# Drones_Schematic_Headers.net
KiCad netlist of a schematic drawn in EAGLE
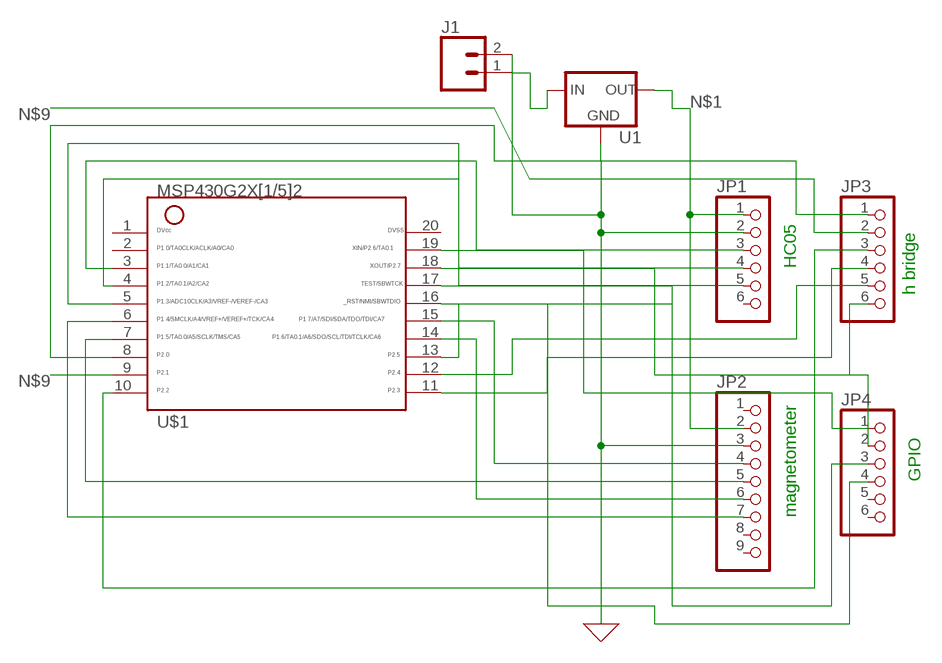
[diagram p0: schematic, sheet 1]

(export (version "E")
  (design (tool "Eeschema 10.0.6"))
  (components
    (comp (ref "J1")
      (value "CONN_025MM")
      (footprint "eagle-import:SCREWTERMINAL-5MM-2")
      (libsource (lib "eagle-import") (part "CONN_025MM"))
    )
    (comp (ref "JP1")
      (value "PINHD-1X6")
      (footprint "eagle-import:1X06")
      (libsource (lib "eagle-import") (part "PINHD-1X6"))
    )
    (comp (ref "JP2")
      (value "PINHD-1X9")
      (footprint "eagle-import:1X09-BIG")
      (libsource (lib "eagle-import") (part "PINHD-1X9"))
    )
    (comp (ref "JP3")
      (value "PINHD-1X6")
      (footprint "eagle-import:1X06")
      (libsource (lib "eagle-import") (part "PINHD-1X6"))
    )
    (comp (ref "JP4")
      (value "PINHD-1X6")
      (footprint "eagle-import:1X06")
      (libsource (lib "eagle-import") (part "PINHD-1X6"))
    )
    (comp (ref "U$1")
      (value "G2X[1/5]2---N20")
      (footprint "eagle-import:N20")
      (libsource (lib "eagle-import") (part "G2X[1/5]2---N20"))
    )
    (comp (ref "U1")
      (value "V_REG_78XXSINK")
      (footprint "eagle-import:TO220-IGO")
      (libsource (lib "eagle-import") (part "V_REG_78XXSINK"))
    )
  )
  (nets
    (net (code "1") (name "/N$1") (class "Default")
      (node (ref "JP1") (pin "1") (pinfunction "1_1") (pintype "passive"))
      (node (ref "JP2") (pin "2") (pinfunction "2_2") (pintype "passive"))
      (node (ref "U1") (pin "OUT") (pinfunction "OUT_OUT") (pintype "passive"))
    )
    (net (code "2") (name "/N$9") (class "Default")
      (node (ref "JP3") (pin "2") (pinfunction "2_2") (pintype "passive"))
      (node (ref "U$1") (pin "9") (pinfunction "9_9") (pintype "bidirectional"))
    )
    (net (code "3") (name "GND") (class "Default")
      (node (ref "J1") (pin "2") (pinfunction "2_2") (pintype "passive"))
      (node (ref "JP1") (pin "2") (pinfunction "2_2") (pintype "passive"))
      (node (ref "JP2") (pin "3") (pinfunction "3_3") (pintype "passive"))
      (node (ref "U1") (pin "GND") (pinfunction "GND_GND") (pintype "input"))
    )
    (net (code "4") (name "Net-(J1-Pad1)") (class "Default")
      (node (ref "J1") (pin "1") (pinfunction "1_1") (pintype "passive"))
      (node (ref "U1") (pin "IN") (pinfunction "IN_IN") (pintype "input"))
    )
    (net (code "5") (name "Net-(JP1-Pad3)") (class "Default")
      (node (ref "JP1") (pin "3") (pinfunction "3_3") (pintype "passive"))
      (node (ref "U$1") (pin "3") (pinfunction "3_3") (pintype "bidirectional"))
    )
    (net (code "6") (name "Net-(JP1-Pad4)") (class "Default")
      (node (ref "JP1") (pin "4") (pinfunction "4_4") (pintype "passive"))
      (node (ref "U$1") (pin "4") (pinfunction "4_4") (pintype "bidirectional"))
    )
    (net (code "7") (name "Net-(JP1-Pad5)") (class "Default")
      (node (ref "JP1") (pin "5") (pinfunction "5_5") (pintype "passive"))
      (node (ref "U$1") (pin "5") (pinfunction "5_5") (pintype "bidirectional"))
    )
    (net (code "8") (name "Net-(JP2-Pad4)") (class "Default")
      (node (ref "JP2") (pin "4") (pinfunction "4_4") (pintype "passive"))
      (node (ref "U$1") (pin "15") (pinfunction "15_15") (pintype "bidirectional"))
    )
    (net (code "9") (name "Net-(JP2-Pad5)") (class "Default")
      (node (ref "JP2") (pin "5") (pinfunction "5_5") (pintype "passive"))
      (node (ref "U$1") (pin "7") (pinfunction "7_7") (pintype "bidirectional"))
    )
    (net (code "10") (name "Net-(JP2-Pad6)") (class "Default")
      (node (ref "JP2") (pin "6") (pinfunction "6_6") (pintype "passive"))
      (node (ref "U$1") (pin "14") (pinfunction "14_14") (pintype "bidirectional"))
    )
    (net (code "11") (name "Net-(JP2-Pad7)") (class "Default")
      (node (ref "JP2") (pin "7") (pinfunction "7_7") (pintype "passive"))
      (node (ref "U$1") (pin "6") (pinfunction "6_6") (pintype "bidirectional"))
    )
    (net (code "12") (name "Net-(JP3-Pad1)") (class "Default")
      (node (ref "JP3") (pin "1") (pinfunction "1_1") (pintype "passive"))
      (node (ref "U$1") (pin "8") (pinfunction "8_8") (pintype "bidirectional"))
    )
    (net (code "13") (name "Net-(JP3-Pad3)") (class "Default")
      (node (ref "JP3") (pin "3") (pinfunction "3_3") (pintype "passive"))
      (node (ref "U$1") (pin "10") (pinfunction "10_10") (pintype "bidirectional"))
    )
    (net (code "14") (name "Net-(JP3-Pad4)") (class "Default")
      (node (ref "JP3") (pin "4") (pinfunction "4_4") (pintype "passive"))
      (node (ref "U$1") (pin "11") (pinfunction "11_11") (pintype "bidirectional"))
    )
    (net (code "15") (name "Net-(JP3-Pad5)") (class "Default")
      (node (ref "JP3") (pin "5") (pinfunction "5_5") (pintype "passive"))
      (node (ref "U$1") (pin "12") (pinfunction "12_12") (pintype "bidirectional"))
    )
    (net (code "16") (name "Net-(JP3-Pad6)") (class "Default")
      (node (ref "JP3") (pin "6") (pinfunction "6_6") (pintype "passive"))
      (node (ref "U$1") (pin "13") (pinfunction "13_13") (pintype "bidirectional"))
    )
    (net (code "17") (name "Net-(JP4-Pad1)") (class "Default")
      (node (ref "JP4") (pin "1") (pinfunction "1_1") (pintype "passive"))
      (node (ref "U$1") (pin "19") (pinfunction "19_19") (pintype "bidirectional"))
    )
    (net (code "18") (name "Net-(JP4-Pad2)") (class "Default")
      (node (ref "JP4") (pin "2") (pinfunction "2_2") (pintype "passive"))
      (node (ref "U$1") (pin "18") (pinfunction "18_18") (pintype "bidirectional"))
    )
    (net (code "19") (name "Net-(JP4-Pad3)") (class "Default")
      (node (ref "JP4") (pin "3") (pinfunction "3_3") (pintype "passive"))
      (node (ref "U$1") (pin "17") (pinfunction "17_17") (pintype "bidirectional"))
    )
    (net (code "20") (name "Net-(JP4-Pad4)") (class "Default")
      (node (ref "JP4") (pin "4") (pinfunction "4_4") (pintype "passive"))
      (node (ref "U$1") (pin "16") (pinfunction "16_16") (pintype "bidirectional"))
    )
    (net (code "21") (name "unconnected-(JP1-Pad6)") (class "Default")
      (node (ref "JP1") (pin "6") (pinfunction "6_6") (pintype "passive"))
    )
    (net (code "22") (name "unconnected-(JP2-Pad1)") (class "Default")
      (node (ref "JP2") (pin "1") (pinfunction "1_1") (pintype "passive"))
    )
    (net (code "23") (name "unconnected-(JP2-Pad8)") (class "Default")
      (node (ref "JP2") (pin "8") (pinfunction "8_8") (pintype "passive"))
    )
    (net (code "24") (name "unconnected-(JP2-Pad9)") (class "Default")
      (node (ref "JP2") (pin "9") (pinfunction "9_9") (pintype "passive"))
    )
    (net (code "25") (name "unconnected-(JP4-Pad5)") (class "Default")
      (node (ref "JP4") (pin "5") (pinfunction "5_5") (pintype "passive"))
    )
    (net (code "26") (name "unconnected-(JP4-Pad6)") (class "Default")
      (node (ref "JP4") (pin "6") (pinfunction "6_6") (pintype "passive"))
    )
    (net (code "27") (name "unconnected-(U$1-Pad1)") (class "Default")
      (node (ref "U$1") (pin "1") (pinfunction "1_1") (pintype "bidirectional"))
    )
    (net (code "28") (name "unconnected-(U$1-Pad2)") (class "Default")
      (node (ref "U$1") (pin "2") (pinfunction "2_2") (pintype "bidirectional"))
    )
    (net (code "29") (name "unconnected-(U$1-Pad20)") (class "Default")
      (node (ref "U$1") (pin "20") (pinfunction "20_20") (pintype "bidirectional"))
    )
  )
)
